# Display_V1_2.net
KiCad netlist of a schematic drawn in EAGLE
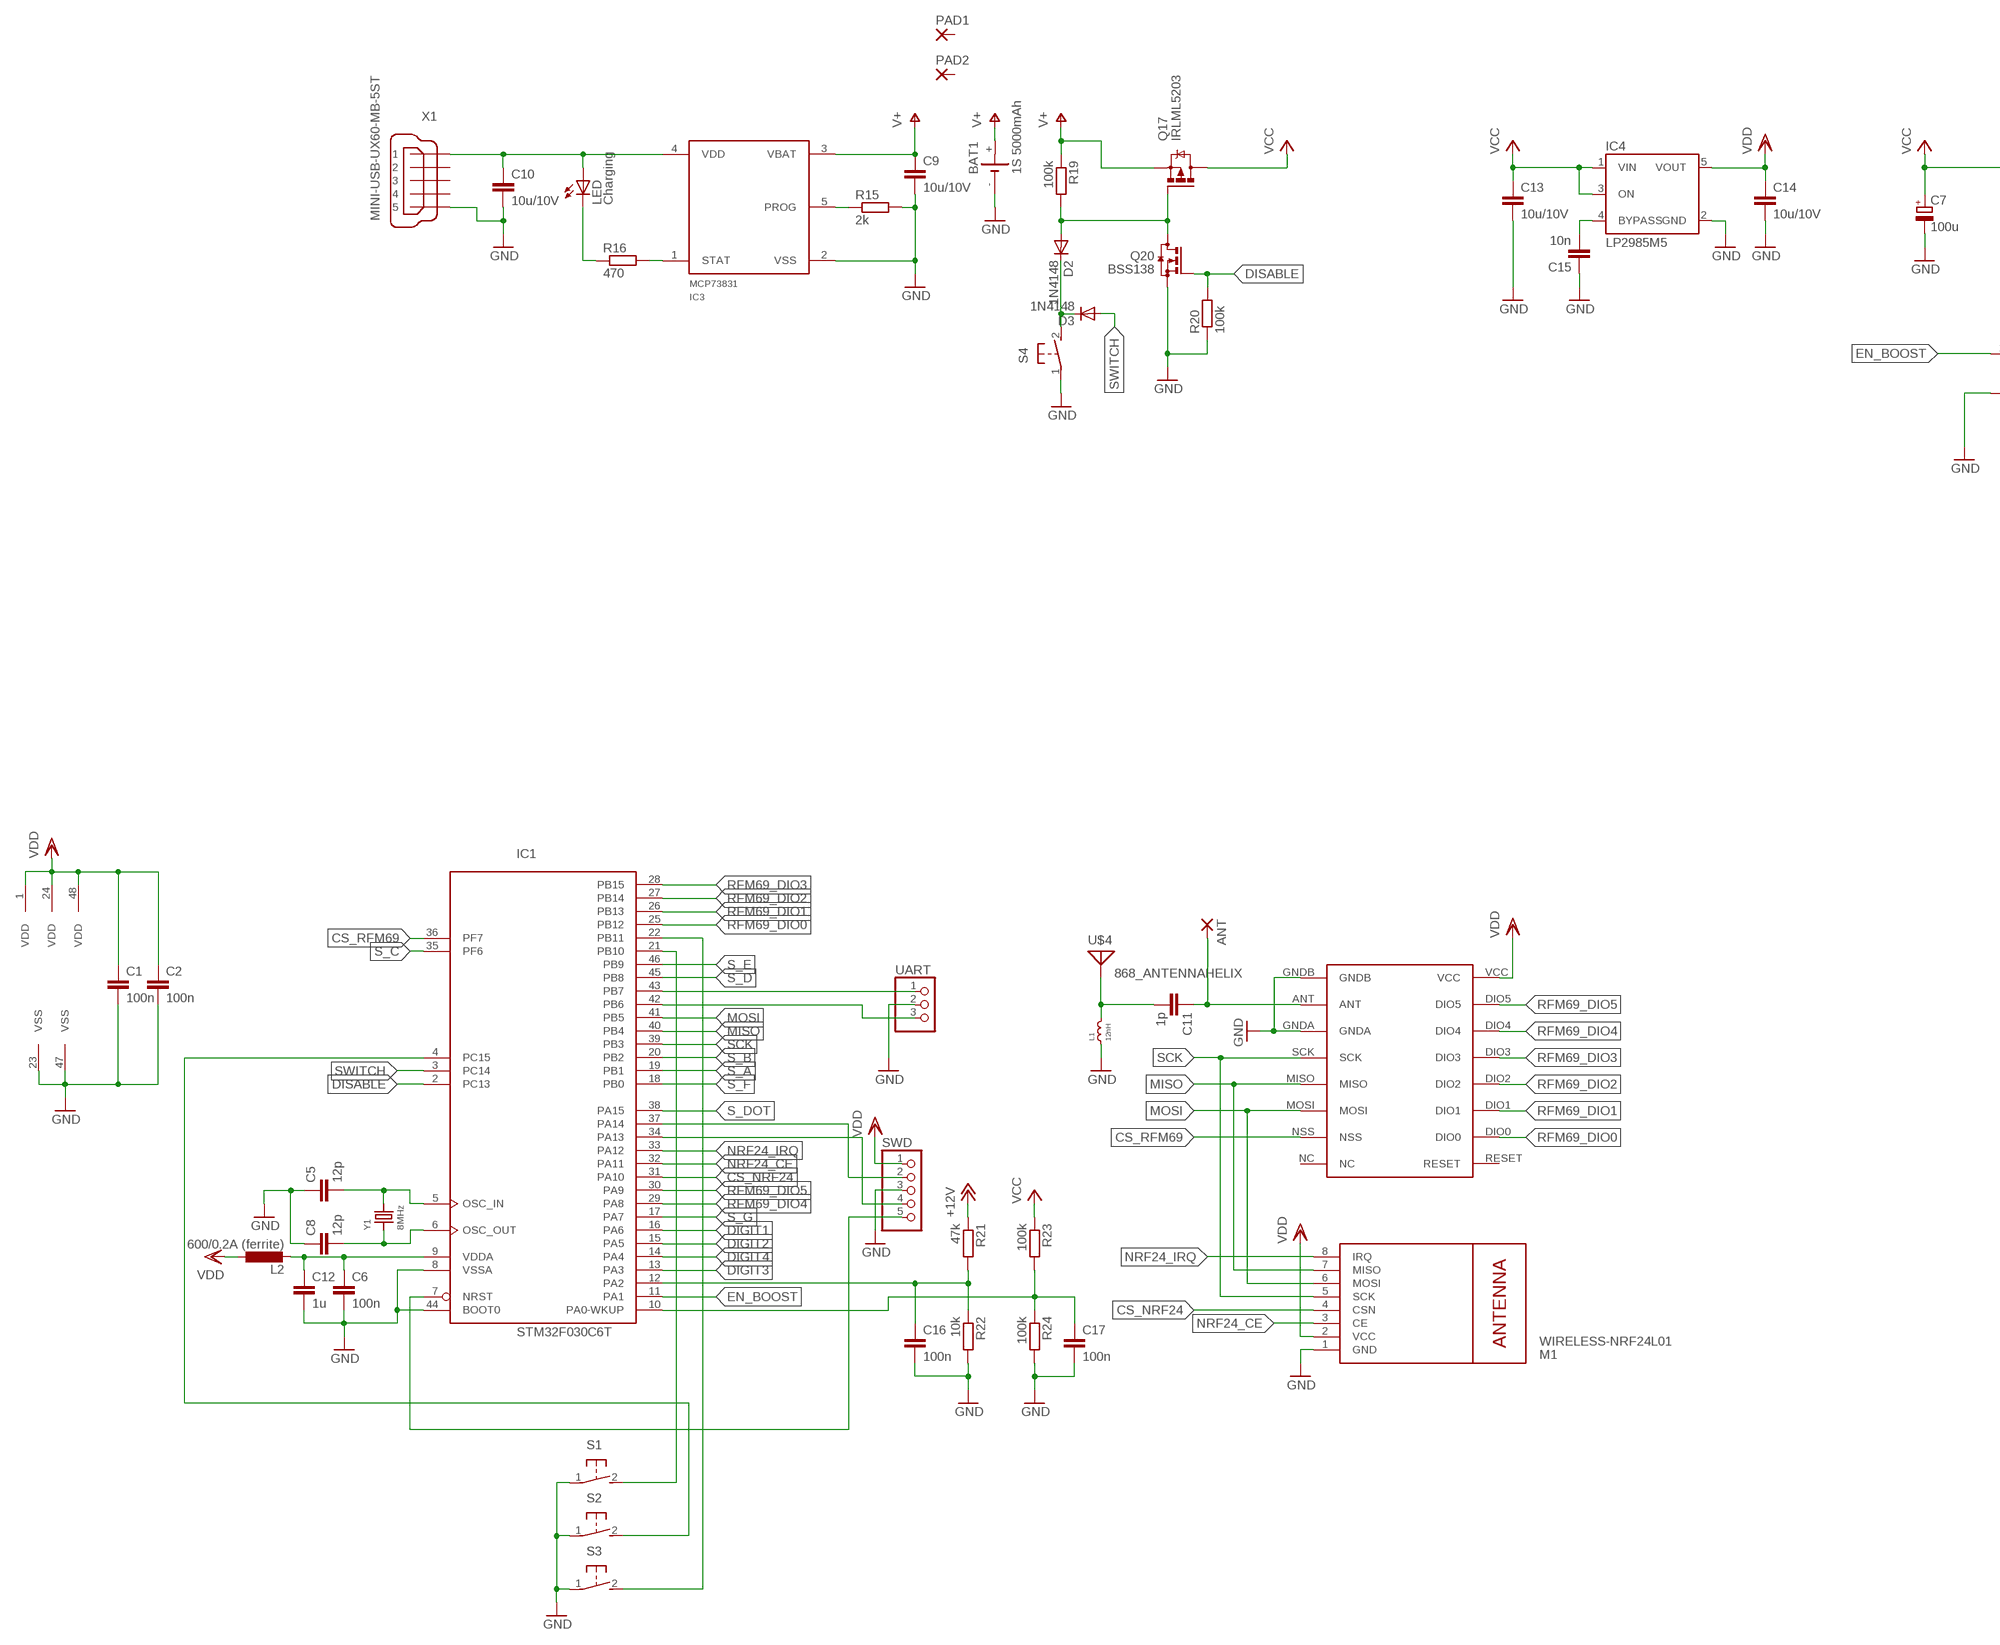
[diagram p0: schematic, sheet 1, part 1 of 2]
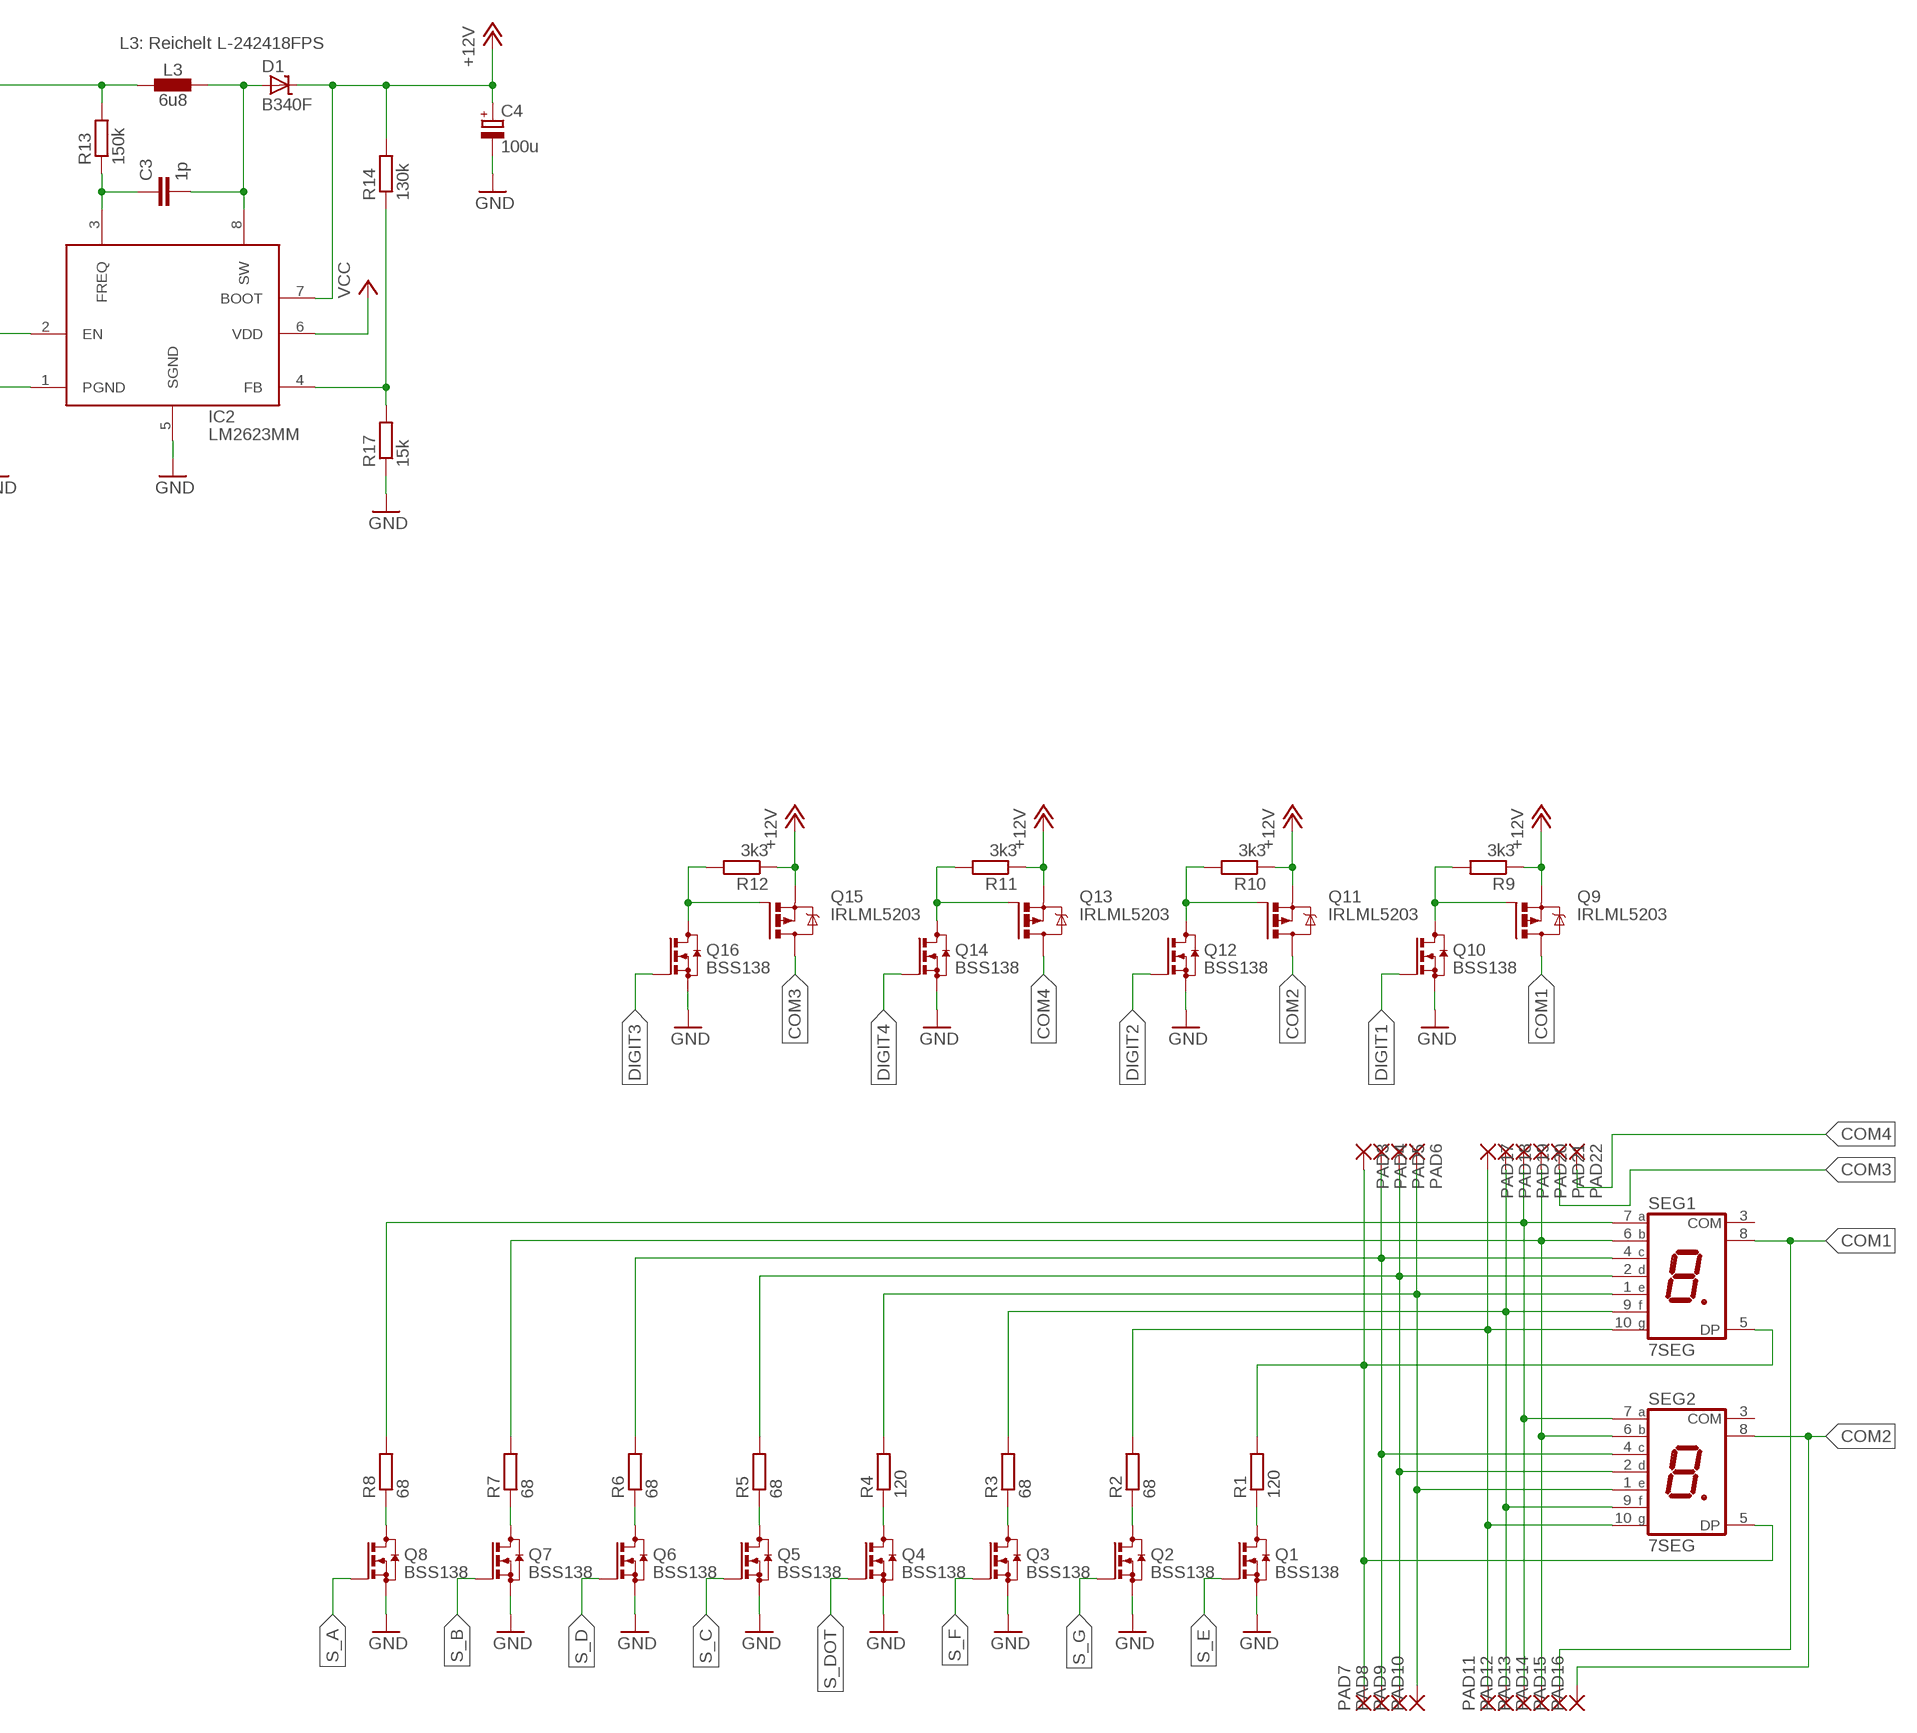
[diagram p1: schematic, sheet 1, part 2 of 2]

(export (version "E")
  (design (tool "Eeschema 10.0.6"))
  (components
    (comp (ref "ANT")
      (value "1,6/0,8")
      (footprint "eagle-import:1,6_0,8")
      (libsource (lib "eagle-import") (part "1,6/0,8"))
    )
    (comp (ref "BAT1")
      (value "1S 5000mAh")
      (footprint "eagle-import:1S_5000MAH")
      (libsource (lib "eagle-import") (part "LIPO"))
    )
    (comp (ref "C1")
      (value "100n")
      (footprint "eagle-import:C0603K")
      (libsource (lib "eagle-import") (part "C-EUC0603K"))
    )
    (comp (ref "C2")
      (value "100n")
      (footprint "eagle-import:C0603K")
      (libsource (lib "eagle-import") (part "C-EUC0603K"))
    )
    (comp (ref "C3")
      (value "1p")
      (footprint "eagle-import:C0603")
      (libsource (lib "eagle-import") (part "C-EUC0603"))
    )
    (comp (ref "C4")
      (value "100u")
      (footprint "eagle-import:153CLV-0605")
      (libsource (lib "eagle-import") (part "CPOL-EU153CLV-0605"))
    )
    (comp (ref "C5")
      (value "12p")
      (footprint "eagle-import:C0603")
      (libsource (lib "eagle-import") (part "C-EUC0603"))
    )
    (comp (ref "C6")
      (value "100n")
      (footprint "eagle-import:C0603")
      (libsource (lib "eagle-import") (part "C-EUC0603"))
    )
    (comp (ref "C7")
      (value "100u")
      (footprint "eagle-import:153CLV-0605")
      (libsource (lib "eagle-import") (part "CPOL-EU153CLV-0605"))
    )
    (comp (ref "C8")
      (value "12p")
      (footprint "eagle-import:C0603")
      (libsource (lib "eagle-import") (part "C-EUC0603"))
    )
    (comp (ref "C9")
      (value "10u/10V")
      (footprint "eagle-import:C1206")
      (libsource (lib "eagle-import") (part "C-EUC1206"))
    )
    (comp (ref "C10")
      (value "10u/10V")
      (footprint "eagle-import:C1206")
      (libsource (lib "eagle-import") (part "C-EUC1206"))
    )
    (comp (ref "C11")
      (value "1p")
      (footprint "eagle-import:C0603")
      (libsource (lib "eagle-import") (part "C-EUC0603"))
    )
    (comp (ref "C12")
      (value "1u")
      (footprint "eagle-import:C0603")
      (libsource (lib "eagle-import") (part "C-EUC0603"))
    )
    (comp (ref "C13")
      (value "10u/10V")
      (footprint "eagle-import:C1206")
      (libsource (lib "eagle-import") (part "C-EUC1206"))
    )
    (comp (ref "C14")
      (value "10u/10V")
      (footprint "eagle-import:C1206")
      (libsource (lib "eagle-import") (part "C-EUC1206"))
    )
    (comp (ref "C15")
      (value "10n")
      (footprint "eagle-import:C0603")
      (libsource (lib "eagle-import") (part "C-EUC0603"))
    )
    (comp (ref "C16")
      (value "100n")
      (footprint "eagle-import:C0603")
      (libsource (lib "eagle-import") (part "C-EUC0603"))
    )
    (comp (ref "C17")
      (value "100n")
      (footprint "eagle-import:C0603")
      (libsource (lib "eagle-import") (part "C-EUC0603"))
    )
    (comp (ref "D1")
      (value "B340F")
      (footprint "eagle-import:SMC")
      (libsource (lib "eagle-import") (part "SD-SMC"))
    )
    (comp (ref "D2")
      (value "1N4148")
      (footprint "eagle-import:MINIMELF")
      (libsource (lib "eagle-import") (part "DIODE-MINIMELF"))
    )
    (comp (ref "D3")
      (value "1N4148")
      (footprint "eagle-import:MINIMELF")
      (libsource (lib "eagle-import") (part "DIODE-MINIMELF"))
    )
    (comp (ref "IC1")
      (value "STM32F030C6T")
      (footprint "eagle-import:LQFP48")
      (libsource (lib "eagle-import") (part "STM32F030CT6"))
    )
    (comp (ref "IC2")
      (value "LM2623MM")
      (footprint "eagle-import:MSOP08")
      (libsource (lib "eagle-import") (part "LM2623MM"))
    )
    (comp (ref "IC3")
      (value "MCP73831")
      (footprint "eagle-import:SOT23-5")
      (libsource (lib "eagle-import") (part "MCP73831"))
    )
    (comp (ref "IC4")
      (value "LP2985M5")
      (footprint "eagle-import:SOT23-5")
      (libsource (lib "eagle-import") (part "LP2985M5"))
    )
    (comp (ref "L1")
      (value "12nH")
      (footprint "eagle-import:0603")
      (libsource (lib "eagle-import") (part "RF-INDUCTOR.0603"))
    )
    (comp (ref "L2")
      (value "600/0.2A (ferrite)")
      (footprint "eagle-import:L2012C")
      (libsource (lib "eagle-import") (part "L-EUL2012C"))
    )
    (comp (ref "L3")
      (value "6u8")
      (footprint "eagle-import:L_NR60XX")
      (libsource (lib "eagle-import") (part "INDUCTOR-NR60XX"))
    )
    (comp (ref "LED")
      (value "Charging")
      (footprint "eagle-import:CHIPLED_0603")
      (libsource (lib "eagle-import") (part "LEDCHIPLED_0603"))
    )
    (comp (ref "M1")
      (value "WIRELESS-NRF24L01")
      (footprint "eagle-import:WIRELESS-NRF24L01")
      (libsource (lib "eagle-import") (part "WIRELESS-NRF24L01"))
    )
    (comp (ref "PAD1")
      (value "2,54/1,0")
      (footprint "eagle-import:2,54_1,0")
      (libsource (lib "eagle-import") (part "2,54/1,0"))
    )
    (comp (ref "PAD2")
      (value "2,54/1,0")
      (footprint "eagle-import:2,54_1,0")
      (libsource (lib "eagle-import") (part "2,54/1,0"))
    )
    (comp (ref "PAD3")
      (value "SMD2")
      (footprint "eagle-import:SMD1,27-2,54")
      (libsource (lib "eagle-import") (part "SMD2"))
    )
    (comp (ref "PAD4")
      (value "SMD2")
      (footprint "eagle-import:SMD1,27-2,54")
      (libsource (lib "eagle-import") (part "SMD2"))
    )
    (comp (ref "PAD5")
      (value "SMD2")
      (footprint "eagle-import:SMD1,27-2,54")
      (libsource (lib "eagle-import") (part "SMD2"))
    )
    (comp (ref "PAD6")
      (value "SMD2")
      (footprint "eagle-import:SMD1,27-2,54")
      (libsource (lib "eagle-import") (part "SMD2"))
    )
    (comp (ref "PAD7")
      (value "SMD2")
      (footprint "eagle-import:SMD1,27-2,54")
      (libsource (lib "eagle-import") (part "SMD2"))
    )
    (comp (ref "PAD8")
      (value "SMD2")
      (footprint "eagle-import:SMD1,27-2,54")
      (libsource (lib "eagle-import") (part "SMD2"))
    )
    (comp (ref "PAD9")
      (value "SMD2")
      (footprint "eagle-import:SMD1,27-2,54")
      (libsource (lib "eagle-import") (part "SMD2"))
    )
    (comp (ref "PAD10")
      (value "SMD2")
      (footprint "eagle-import:SMD1,27-2,54")
      (libsource (lib "eagle-import") (part "SMD2"))
    )
    (comp (ref "PAD11")
      (value "SMD2")
      (footprint "eagle-import:SMD1,27-2,54")
      (libsource (lib "eagle-import") (part "SMD2"))
    )
    (comp (ref "PAD12")
      (value "SMD2")
      (footprint "eagle-import:SMD1,27-2,54")
      (libsource (lib "eagle-import") (part "SMD2"))
    )
    (comp (ref "PAD13")
      (value "SMD2")
      (footprint "eagle-import:SMD1,27-2,54")
      (libsource (lib "eagle-import") (part "SMD2"))
    )
    (comp (ref "PAD14")
      (value "SMD2")
      (footprint "eagle-import:SMD1,27-2,54")
      (libsource (lib "eagle-import") (part "SMD2"))
    )
    (comp (ref "PAD15")
      (value "SMD2")
      (footprint "eagle-import:SMD1,27-2,54")
      (libsource (lib "eagle-import") (part "SMD2"))
    )
    (comp (ref "PAD16")
      (value "SMD2")
      (footprint "eagle-import:SMD1,27-2,54")
      (libsource (lib "eagle-import") (part "SMD2"))
    )
    (comp (ref "PAD17")
      (value "SMD2")
      (footprint "eagle-import:SMD1,27-2,54")
      (libsource (lib "eagle-import") (part "SMD2"))
    )
    (comp (ref "PAD18")
      (value "SMD2")
      (footprint "eagle-import:SMD1,27-2,54")
      (libsource (lib "eagle-import") (part "SMD2"))
    )
    (comp (ref "PAD19")
      (value "SMD2")
      (footprint "eagle-import:SMD1,27-2,54")
      (libsource (lib "eagle-import") (part "SMD2"))
    )
    (comp (ref "PAD20")
      (value "SMD2")
      (footprint "eagle-import:SMD1,27-2,54")
      (libsource (lib "eagle-import") (part "SMD2"))
    )
    (comp (ref "PAD21")
      (value "SMD2")
      (footprint "eagle-import:SMD1,27-2,54")
      (libsource (lib "eagle-import") (part "SMD2"))
    )
    (comp (ref "PAD22")
      (value "SMD2")
      (footprint "eagle-import:SMD1,27-2,54")
      (libsource (lib "eagle-import") (part "SMD2"))
    )
    (comp (ref "Q1")
      (value "BSS138")
      (footprint "eagle-import:SOT23")
      (libsource (lib "eagle-import") (part "BSS123"))
    )
    (comp (ref "Q2")
      (value "BSS138")
      (footprint "eagle-import:SOT23")
      (libsource (lib "eagle-import") (part "BSS123"))
    )
    (comp (ref "Q3")
      (value "BSS138")
      (footprint "eagle-import:SOT23")
      (libsource (lib "eagle-import") (part "BSS123"))
    )
    (comp (ref "Q4")
      (value "BSS138")
      (footprint "eagle-import:SOT23")
      (libsource (lib "eagle-import") (part "BSS123"))
    )
    (comp (ref "Q5")
      (value "BSS138")
      (footprint "eagle-import:SOT23")
      (libsource (lib "eagle-import") (part "BSS123"))
    )
    (comp (ref "Q6")
      (value "BSS138")
      (footprint "eagle-import:SOT23")
      (libsource (lib "eagle-import") (part "BSS123"))
    )
    (comp (ref "Q7")
      (value "BSS138")
      (footprint "eagle-import:SOT23")
      (libsource (lib "eagle-import") (part "BSS123"))
    )
    (comp (ref "Q8")
      (value "BSS138")
      (footprint "eagle-import:SOT23")
      (libsource (lib "eagle-import") (part "BSS123"))
    )
    (comp (ref "Q9")
      (value "IRLML5203")
      (footprint "eagle-import:MICRO3")
      (libsource (lib "eagle-import") (part "IRLML5203"))
    )
    (comp (ref "Q10")
      (value "BSS138")
      (footprint "eagle-import:SOT23")
      (libsource (lib "eagle-import") (part "BSS123"))
    )
    (comp (ref "Q11")
      (value "IRLML5203")
      (footprint "eagle-import:MICRO3")
      (libsource (lib "eagle-import") (part "IRLML5203"))
    )
    (comp (ref "Q12")
      (value "BSS138")
      (footprint "eagle-import:SOT23")
      (libsource (lib "eagle-import") (part "BSS123"))
    )
    (comp (ref "Q13")
      (value "IRLML5203")
      (footprint "eagle-import:MICRO3")
      (libsource (lib "eagle-import") (part "IRLML5203"))
    )
    (comp (ref "Q14")
      (value "BSS138")
      (footprint "eagle-import:SOT23")
      (libsource (lib "eagle-import") (part "BSS123"))
    )
    (comp (ref "Q15")
      (value "IRLML5203")
      (footprint "eagle-import:MICRO3")
      (libsource (lib "eagle-import") (part "IRLML5203"))
    )
    (comp (ref "Q16")
      (value "BSS138")
      (footprint "eagle-import:SOT23")
      (libsource (lib "eagle-import") (part "BSS123"))
    )
    (comp (ref "Q17")
      (value "IRLML5203")
      (footprint "eagle-import:MICRO3")
      (libsource (lib "eagle-import") (part "IRLML5203"))
    )
    (comp (ref "Q20")
      (value "BSS138")
      (footprint "eagle-import:SOT23")
      (libsource (lib "eagle-import") (part "BSS123"))
    )
    (comp (ref "R1")
      (value "120")
      (footprint "eagle-import:R1206")
      (libsource (lib "eagle-import") (part "R-EU_R1206"))
    )
    (comp (ref "R2")
      (value "68")
      (footprint "eagle-import:R1206")
      (libsource (lib "eagle-import") (part "R-EU_R1206"))
    )
    (comp (ref "R3")
      (value "68")
      (footprint "eagle-import:R1206")
      (libsource (lib "eagle-import") (part "R-EU_R1206"))
    )
    (comp (ref "R4")
      (value "120")
      (footprint "eagle-import:R1206")
      (libsource (lib "eagle-import") (part "R-EU_R1206"))
    )
    (comp (ref "R5")
      (value "68")
      (footprint "eagle-import:R1206")
      (libsource (lib "eagle-import") (part "R-EU_R1206"))
    )
    (comp (ref "R6")
      (value "68")
      (footprint "eagle-import:R1206")
      (libsource (lib "eagle-import") (part "R-EU_R1206"))
    )
    (comp (ref "R7")
      (value "68")
      (footprint "eagle-import:R1206")
      (libsource (lib "eagle-import") (part "R-EU_R1206"))
    )
    (comp (ref "R8")
      (value "68")
      (footprint "eagle-import:R1206")
      (libsource (lib "eagle-import") (part "R-EU_R1206"))
    )
    (comp (ref "R9")
      (value "3k3")
      (footprint "eagle-import:R0603")
      (libsource (lib "eagle-import") (part "resistor_R-EU_R0603"))
    )
    (comp (ref "R10")
      (value "3k3")
      (footprint "eagle-import:R0603")
      (libsource (lib "eagle-import") (part "resistor_R-EU_R0603"))
    )
    (comp (ref "R11")
      (value "3k3")
      (footprint "eagle-import:R0603")
      (libsource (lib "eagle-import") (part "resistor_R-EU_R0603"))
    )
    (comp (ref "R12")
      (value "3k3")
      (footprint "eagle-import:R0603")
      (libsource (lib "eagle-import") (part "resistor_R-EU_R0603"))
    )
    (comp (ref "R13")
      (value "150k")
      (footprint "eagle-import:R0603")
      (libsource (lib "eagle-import") (part "R-EU_R0603"))
    )
    (comp (ref "R14")
      (value "130k")
      (footprint "eagle-import:R0603")
      (libsource (lib "eagle-import") (part "R-EU_R0603"))
    )
    (comp (ref "R15")
      (value "2k")
      (footprint "eagle-import:R0603")
      (libsource (lib "eagle-import") (part "R-EU_R0603"))
    )
    (comp (ref "R16")
      (value "470")
      (footprint "eagle-import:R0603")
      (libsource (lib "eagle-import") (part "R-EU_R0603"))
    )
    (comp (ref "R17")
      (value "15k")
      (footprint "eagle-import:R0603")
      (libsource (lib "eagle-import") (part "R-EU_R0603"))
    )
    (comp (ref "R19")
      (value "100k")
      (footprint "eagle-import:R0603")
      (libsource (lib "eagle-import") (part "R-EU_R0603"))
    )
    (comp (ref "R20")
      (value "100k")
      (footprint "eagle-import:R0603")
      (libsource (lib "eagle-import") (part "R-EU_R0603"))
    )
    (comp (ref "R21")
      (value "47k")
      (footprint "eagle-import:R0603")
      (libsource (lib "eagle-import") (part "R-EU_R0603"))
    )
    (comp (ref "R22")
      (value "10k")
      (footprint "eagle-import:R0603")
      (libsource (lib "eagle-import") (part "R-EU_R0603"))
    )
    (comp (ref "R23")
      (value "100k")
      (footprint "eagle-import:R0603")
      (libsource (lib "eagle-import") (part "R-EU_R0603"))
    )
    (comp (ref "R24")
      (value "100k")
      (footprint "eagle-import:R0603")
      (libsource (lib "eagle-import") (part "R-EU_R0603"))
    )
    (comp (ref "S1")
      (value "31-XX")
      (footprint "eagle-import:B3F-31XX")
      (fields (field (name "MPN") "B3F-3100"))
      (libsource (lib "eagle-import") (part "31-XX"))
    )
    (comp (ref "S2")
      (value "31-XX")
      (footprint "eagle-import:B3F-31XX")
      (fields (field (name "MPN") "B3F-3100"))
      (libsource (lib "eagle-import") (part "31-XX"))
    )
    (comp (ref "S3")
      (value "31-XX")
      (footprint "eagle-import:B3F-31XX")
      (fields (field (name "MPN") "B3F-3100"))
      (libsource (lib "eagle-import") (part "31-XX"))
    )
    (comp (ref "S4")
      (value "31-XX")
      (footprint "eagle-import:B3F-31XX")
      (fields (field (name "MPN") "B3F-3100"))
      (libsource (lib "eagle-import") (part "31-XX"))
    )
    (comp (ref "SEG1")
      (value "7SEG")
      (footprint "eagle-import:7SEG_70_40")
      (libsource (lib "eagle-import") (part "7SEG"))
    )
    (comp (ref "SEG2")
      (value "7SEG")
      (footprint "eagle-import:7SEG_70_40")
      (libsource (lib "eagle-import") (part "7SEG"))
    )
    (comp (ref "SWD")
      (value "PINHD-1X5")
      (footprint "eagle-import:1X05")
      (libsource (lib "eagle-import") (part "PINHD-1X5"))
    )
    (comp (ref "U$1")
      (value "RFM69HW")
      (footprint "eagle-import:RFM")
      (libsource (lib "eagle-import") (part "RFM69HW"))
    )
    (comp (ref "U$4")
      (value "868_ANTENNAHELIX")
      (footprint "eagle-import:HELIX_868")
      (libsource (lib "eagle-import") (part "868_ANTENNAHELIX"))
    )
    (comp (ref "UART")
      (value "PINHD-1X3")
      (footprint "eagle-import:1X03")
      (libsource (lib "eagle-import") (part "PINHD-1X3"))
    )
    (comp (ref "X1")
      (value "MINI-USB-UX60-MB-5ST")
      (footprint "eagle-import:UX60-MB-5ST")
      (libsource (lib "eagle-import") (part "MINI-USB-UX60-MB-5ST"))
    )
    (comp (ref "Y1")
      (value "8MHz")
      (footprint "eagle-import:3.2X2.5MM")
      (libsource (lib "eagle-import") (part "CRYSTAL.3.2X2.5MM"))
    )
  )
  (nets
    (net (code "1") (name "+12V") (class "Default")
      (node (ref "C4") (pin "+") (pinfunction "+_+") (pintype "passive"))
      (node (ref "D1") (pin "C") (pinfunction "C_C") (pintype "passive"))
      (node (ref "IC2") (pin "7") (pinfunction "BOOT_7") (pintype "bidirectional"))
      (node (ref "Q11") (pin "2") (pinfunction "S_2") (pintype "passive"))
      (node (ref "Q13") (pin "2") (pinfunction "S_2") (pintype "passive"))
      (node (ref "Q15") (pin "2") (pinfunction "S_2") (pintype "passive"))
      (node (ref "Q9") (pin "2") (pinfunction "S_2") (pintype "passive"))
      (node (ref "R10") (pin "1") (pinfunction "1_1") (pintype "passive"))
      (node (ref "R11") (pin "1") (pinfunction "1_1") (pintype "passive"))
      (node (ref "R12") (pin "1") (pinfunction "1_1") (pintype "passive"))
      (node (ref "R14") (pin "2") (pinfunction "2_2") (pintype "passive"))
      (node (ref "R21") (pin "1") (pinfunction "1_1") (pintype "passive"))
      (node (ref "R9") (pin "1") (pinfunction "1_1") (pintype "passive"))
    )
    (net (code "2") (name "COM1") (class "Default")
      (node (ref "PAD15") (pin "1") (pinfunction "P_1") (pintype "passive"))
      (node (ref "Q9") (pin "3") (pinfunction "D_3") (pintype "passive"))
      (node (ref "SEG1") (pin "8") (pinfunction "COM_8") (pintype "passive"))
    )
    (net (code "3") (name "COM2") (class "Default")
      (node (ref "PAD16") (pin "1") (pinfunction "P_1") (pintype "passive"))
      (node (ref "Q11") (pin "3") (pinfunction "D_3") (pintype "passive"))
      (node (ref "SEG2") (pin "8") (pinfunction "COM_8") (pintype "passive"))
    )
    (net (code "4") (name "COM3") (class "Default")
      (node (ref "PAD21") (pin "1") (pinfunction "P_1") (pintype "passive"))
      (node (ref "Q15") (pin "3") (pinfunction "D_3") (pintype "passive"))
    )
    (net (code "5") (name "COM4") (class "Default")
      (node (ref "PAD22") (pin "1") (pinfunction "P_1") (pintype "passive"))
      (node (ref "Q13") (pin "3") (pinfunction "D_3") (pintype "passive"))
    )
    (net (code "6") (name "CS_NRF24") (class "Default")
      (node (ref "IC1") (pin "31") (pinfunction "PA10_31") (pintype "bidirectional"))
      (node (ref "M1") (pin "4") (pinfunction "CSN_4") (pintype "bidirectional"))
    )
    (net (code "7") (name "CS_RFM69") (class "Default")
      (node (ref "IC1") (pin "36") (pinfunction "PF7_36") (pintype "bidirectional"))
      (node (ref "U$1") (pin "NSS") (pinfunction "NSS_NSS") (pintype "bidirectional"))
    )
    (net (code "8") (name "DIGIT1") (class "Default")
      (node (ref "IC1") (pin "16") (pinfunction "PA6_16") (pintype "bidirectional"))
      (node (ref "Q10") (pin "1") (pinfunction "G_1") (pintype "passive"))
    )
    (net (code "9") (name "DIGIT2") (class "Default")
      (node (ref "IC1") (pin "15") (pinfunction "PA5_15") (pintype "bidirectional"))
      (node (ref "Q12") (pin "1") (pinfunction "G_1") (pintype "passive"))
    )
    (net (code "10") (name "DIGIT3") (class "Default")
      (node (ref "IC1") (pin "13") (pinfunction "PA3_13") (pintype "bidirectional"))
      (node (ref "Q16") (pin "1") (pinfunction "G_1") (pintype "passive"))
    )
    (net (code "11") (name "DIGIT4") (class "Default")
      (node (ref "IC1") (pin "14") (pinfunction "PA4_14") (pintype "bidirectional"))
      (node (ref "Q14") (pin "1") (pinfunction "G_1") (pintype "passive"))
    )
    (net (code "12") (name "DISABLE") (class "Default")
      (node (ref "IC1") (pin "2") (pinfunction "PC13_2") (pintype "bidirectional"))
      (node (ref "Q20") (pin "1") (pinfunction "G_1") (pintype "passive"))
      (node (ref "R20") (pin "2") (pinfunction "2_2") (pintype "passive"))
    )
    (net (code "13") (name "EN_BOOST") (class "Default")
      (node (ref "IC1") (pin "11") (pinfunction "PA1_11") (pintype "bidirectional"))
      (node (ref "IC2") (pin "2") (pinfunction "EN_2") (pintype "bidirectional"))
    )
    (net (code "14") (name "GND") (class "Default")
      (node (ref "BAT1") (pin "-") (pinfunction "-_-") (pintype "passive"))
      (node (ref "C1") (pin "2") (pinfunction "2_2") (pintype "passive"))
      (node (ref "C10") (pin "2") (pinfunction "2_2") (pintype "passive"))
      (node (ref "C12") (pin "2") (pinfunction "2_2") (pintype "passive"))
      (node (ref "C13") (pin "2") (pinfunction "2_2") (pintype "passive"))
      (node (ref "C14") (pin "2") (pinfunction "2_2") (pintype "passive"))
      (node (ref "C15") (pin "1") (pinfunction "1_1") (pintype "passive"))
      (node (ref "C16") (pin "2") (pinfunction "2_2") (pintype "passive"))
      (node (ref "C17") (pin "2") (pinfunction "2_2") (pintype "passive"))
      (node (ref "C2") (pin "2") (pinfunction "2_2") (pintype "passive"))
      (node (ref "C4") (pin "-") (pinfunction "-_-") (pintype "passive"))
      (node (ref "C5") (pin "1") (pinfunction "1_1") (pintype "passive"))
      (node (ref "C6") (pin "2") (pinfunction "2_2") (pintype "passive"))
      (node (ref "C7") (pin "-") (pinfunction "-_-") (pintype "passive"))
      (node (ref "C8") (pin "1") (pinfunction "1_1") (pintype "passive"))
      (node (ref "C9") (pin "2") (pinfunction "2_2") (pintype "passive"))
      (node (ref "IC1") (pin "23") (pinfunction "VSS_23") (pintype "power_in"))
      (node (ref "IC1") (pin "44") (pinfunction "BOOT0_44") (pintype "input"))
      (node (ref "IC1") (pin "47") (pinfunction "VSS_47") (pintype "power_in"))
      (node (ref "IC1") (pin "8") (pinfunction "VSSA_8") (pintype "power_in"))
      (node (ref "IC2") (pin "1") (pinfunction "PGND_1") (pintype "bidirectional"))
      (node (ref "IC2") (pin "5") (pinfunction "SGND_5") (pintype "bidirectional"))
      (node (ref "IC3") (pin "2") (pinfunction "VSS_2") (pintype "bidirectional"))
      (node (ref "IC4") (pin "2") (pinfunction "GND_2") (pintype "power_in"))
      (node (ref "L1") (pin "1") (pinfunction "1_1") (pintype "passive"))
      (node (ref "M1") (pin "1") (pinfunction "GND_1") (pintype "power_in"))
      (node (ref "Q1") (pin "2") (pinfunction "S_2") (pintype "passive"))
      (node (ref "Q10") (pin "2") (pinfunction "S_2") (pintype "passive"))
      (node (ref "Q12") (pin "2") (pinfunction "S_2") (pintype "passive"))
      (node (ref "Q14") (pin "2") (pinfunction "S_2") (pintype "passive"))
      (node (ref "Q16") (pin "2") (pinfunction "S_2") (pintype "passive"))
      (node (ref "Q2") (pin "2") (pinfunction "S_2") (pintype "passive"))
      (node (ref "Q20") (pin "2") (pinfunction "S_2") (pintype "passive"))
      (node (ref "Q3") (pin "2") (pinfunction "S_2") (pintype "passive"))
      (node (ref "Q4") (pin "2") (pinfunction "S_2") (pintype "passive"))
      (node (ref "Q5") (pin "2") (pinfunction "S_2") (pintype "passive"))
      (node (ref "Q6") (pin "2") (pinfunction "S_2") (pintype "passive"))
      (node (ref "Q7") (pin "2") (pinfunction "S_2") (pintype "passive"))
      (node (ref "Q8") (pin "2") (pinfunction "S_2") (pintype "passive"))
      (node (ref "R15") (pin "2") (pinfunction "2_2") (pintype "passive"))
      (node (ref "R17") (pin "1") (pinfunction "1_1") (pintype "passive"))
      (node (ref "R20") (pin "1") (pinfunction "1_1") (pintype "passive"))
      (node (ref "R22") (pin "2") (pinfunction "2_2") (pintype "passive"))
      (node (ref "R24") (pin "2") (pinfunction "2_2") (pintype "passive"))
      (node (ref "S1") (pin "1") (pinfunction "P_1") (pintype "passive"))
      (node (ref "S2") (pin "1") (pinfunction "P_1") (pintype "passive"))
      (node (ref "S3") (pin "1") (pinfunction "P_1") (pintype "passive"))
      (node (ref "S4") (pin "1") (pinfunction "P_1") (pintype "passive"))
      (node (ref "SWD") (pin "3") (pinfunction "3_3") (pintype "passive"))
      (node (ref "U$1") (pin "GNDA") (pinfunction "GNDA_GNDA") (pintype "bidirectional"))
      (node (ref "U$1") (pin "GNDB") (pinfunction "GNDB_GNDB") (pintype "bidirectional"))
      (node (ref "UART") (pin "2") (pinfunction "2_2") (pintype "passive"))
      (node (ref "X1") (pin "5") (pinfunction "5_5") (pintype "input"))
    )
    (net (code "15") (name "MISO") (class "Default")
      (node (ref "IC1") (pin "40") (pinfunction "PB4_40") (pintype "bidirectional"))
      (node (ref "M1") (pin "7") (pinfunction "MISO_7") (pintype "bidirectional"))
      (node (ref "U$1") (pin "MISO") (pinfunction "MISO_MISO") (pintype "bidirectional"))
    )
    (net (code "16") (name "MOSI") (class "Default")
      (node (ref "IC1") (pin "41") (pinfunction "PB5_41") (pintype "bidirectional"))
      (node (ref "M1") (pin "6") (pinfunction "MOSI_6") (pintype "bidirectional"))
      (node (ref "U$1") (pin "MOSI") (pinfunction "MOSI_MOSI") (pintype "bidirectional"))
    )
    (net (code "17") (name "NRF24_CE") (class "Default")
      (node (ref "IC1") (pin "32") (pinfunction "PA11_32") (pintype "bidirectional"))
      (node (ref "M1") (pin "3") (pinfunction "CE_3") (pintype "bidirectional"))
    )
    (net (code "18") (name "NRF24_IRQ") (class "Default")
      (node (ref "IC1") (pin "33") (pinfunction "PA12_33") (pintype "bidirectional"))
      (node (ref "M1") (pin "8") (pinfunction "IRQ_8") (pintype "bidirectional"))
    )
    (net (code "19") (name "Net-(ANT-P)") (class "Default")
      (node (ref "ANT") (pin "1") (pinfunction "P_1") (pintype "passive"))
      (node (ref "C11") (pin "1") (pinfunction "1_1") (pintype "passive"))
      (node (ref "U$1") (pin "ANT") (pinfunction "ANT_ANT") (pintype "bidirectional"))
    )
    (net (code "20") (name "Net-(C11-Pad2)") (class "Default")
      (node (ref "C11") (pin "2") (pinfunction "2_2") (pintype "passive"))
      (node (ref "L1") (pin "2") (pinfunction "2_2") (pintype "passive"))
      (node (ref "U$4") (pin "ANT") (pinfunction "1_ANT") (pintype "output"))
      (node (ref "U$4") (pin "P$10") (pinfunction "1_P$10") (pintype "output"))
      (node (ref "U$4") (pin "P$11") (pinfunction "1_P$11") (pintype "output"))
      (node (ref "U$4") (pin "P$12") (pinfunction "1_P$12") (pintype "output"))
      (node (ref "U$4") (pin "P$13") (pinfunction "1_P$13") (pintype "output"))
      (node (ref "U$4") (pin "P$14") (pinfunction "1_P$14") (pintype "output"))
      (node (ref "U$4") (pin "P$15") (pinfunction "1_P$15") (pintype "output"))
      (node (ref "U$4") (pin "P$16") (pinfunction "1_P$16") (pintype "output"))
      (node (ref "U$4") (pin "P$17") (pinfunction "1_P$17") (pintype "output"))
      (node (ref "U$4") (pin "P$18") (pinfunction "1_P$18") (pintype "output"))
      (node (ref "U$4") (pin "P$19") (pinfunction "1_P$19") (pintype "output"))
      (node (ref "U$4") (pin "P$2") (pinfunction "1_P$2") (pintype "output"))
      (node (ref "U$4") (pin "P$20") (pinfunction "1_P$20") (pintype "output"))
      (node (ref "U$4") (pin "P$3") (pinfunction "1_P$3") (pintype "output"))
      (node (ref "U$4") (pin "P$4") (pinfunction "1_P$4") (pintype "output"))
      (node (ref "U$4") (pin "P$5") (pinfunction "1_P$5") (pintype "output"))
      (node (ref "U$4") (pin "P$6") (pinfunction "1_P$6") (pintype "output"))
      (node (ref "U$4") (pin "P$7") (pinfunction "1_P$7") (pintype "output"))
      (node (ref "U$4") (pin "P$8") (pinfunction "1_P$8") (pintype "output"))
      (node (ref "U$4") (pin "P$9") (pinfunction "1_P$9") (pintype "output"))
    )
    (net (code "21") (name "Net-(IC1A-NRST)") (class "Default")
      (node (ref "IC1") (pin "7") (pinfunction "NRST_7") (pintype "bidirectional"))
      (node (ref "SWD") (pin "5") (pinfunction "5_5") (pintype "passive"))
    )
    (net (code "22") (name "Net-(IC1A-OSC_IN)") (class "Default")
      (node (ref "C5") (pin "2") (pinfunction "2_2") (pintype "passive"))
      (node (ref "IC1") (pin "5") (pinfunction "OSC_IN_5") (pintype "bidirectional"))
      (node (ref "Y1") (pin "3") (pinfunction "2_3") (pintype "passive"))
    )
    (net (code "23") (name "Net-(IC1A-OSC_OUT)") (class "Default")
      (node (ref "C8") (pin "2") (pinfunction "2_2") (pintype "passive"))
      (node (ref "IC1") (pin "6") (pinfunction "OSC_OUT_6") (pintype "bidirectional"))
      (node (ref "Y1") (pin "1") (pinfunction "1_1") (pintype "passive"))
    )
    (net (code "24") (name "Net-(IC1A-PA0-WKUP)") (class "Default")
      (node (ref "C17") (pin "1") (pinfunction "1_1") (pintype "passive"))
      (node (ref "IC1") (pin "10") (pinfunction "PA0-WKUP_10") (pintype "bidirectional"))
      (node (ref "R23") (pin "2") (pinfunction "2_2") (pintype "passive"))
      (node (ref "R24") (pin "1") (pinfunction "1_1") (pintype "passive"))
    )
    (net (code "25") (name "Net-(IC1A-PA2)") (class "Default")
      (node (ref "C16") (pin "1") (pinfunction "1_1") (pintype "passive"))
      (node (ref "IC1") (pin "12") (pinfunction "PA2_12") (pintype "bidirectional"))
      (node (ref "R21") (pin "2") (pinfunction "2_2") (pintype "passive"))
      (node (ref "R22") (pin "1") (pinfunction "1_1") (pintype "passive"))
    )
    (net (code "26") (name "Net-(IC1A-PA13)") (class "Default")
      (node (ref "IC1") (pin "34") (pinfunction "PA13_34") (pintype "bidirectional"))
      (node (ref "SWD") (pin "4") (pinfunction "4_4") (pintype "passive"))
    )
    (net (code "27") (name "Net-(IC1A-PA14)") (class "Default")
      (node (ref "IC1") (pin "37") (pinfunction "PA14_37") (pintype "bidirectional"))
      (node (ref "SWD") (pin "2") (pinfunction "2_2") (pintype "passive"))
    )
    (net (code "28") (name "Net-(IC1A-PB6)") (class "Default")
      (node (ref "IC1") (pin "42") (pinfunction "PB6_42") (pintype "bidirectional"))
      (node (ref "UART") (pin "3") (pinfunction "3_3") (pintype "passive"))
    )
    (net (code "29") (name "Net-(IC1A-PB7)") (class "Default")
      (node (ref "IC1") (pin "43") (pinfunction "PB7_43") (pintype "bidirectional"))
      (node (ref "UART") (pin "1") (pinfunction "1_1") (pintype "passive"))
    )
    (net (code "30") (name "Net-(IC1A-PB10)") (class "Default")
      (node (ref "IC1") (pin "21") (pinfunction "PB10_21") (pintype "bidirectional"))
      (node (ref "S1") (pin "2") (pinfunction "S_2") (pintype "passive"))
    )
    (net (code "31") (name "Net-(IC1A-PB11)") (class "Default")
      (node (ref "IC1") (pin "22") (pinfunction "PB11_22") (pintype "bidirectional"))
      (node (ref "S3") (pin "2") (pinfunction "S_2") (pintype "passive"))
    )
    (net (code "32") (name "Net-(IC1A-PC15)") (class "Default")
      (node (ref "IC1") (pin "4") (pinfunction "PC15_4") (pintype "bidirectional"))
      (node (ref "S2") (pin "2") (pinfunction "S_2") (pintype "passive"))
    )
    (net (code "33") (name "Net-(IC1A-VDDA)") (class "Default")
      (node (ref "C12") (pin "1") (pinfunction "1_1") (pintype "passive"))
      (node (ref "C6") (pin "1") (pinfunction "1_1") (pintype "passive"))
      (node (ref "IC1") (pin "9") (pinfunction "VDDA_9") (pintype "power_in"))
      (node (ref "L2") (pin "2") (pinfunction "2_2") (pintype "passive"))
    )
    (net (code "34") (name "Net-(IC2-FB)") (class "Default")
      (node (ref "IC2") (pin "4") (pinfunction "FB_4") (pintype "bidirectional"))
      (node (ref "R14") (pin "1") (pinfunction "1_1") (pintype "passive"))
      (node (ref "R17") (pin "2") (pinfunction "2_2") (pintype "passive"))
    )
    (net (code "35") (name "Net-(IC2-FREQ)") (class "Default")
      (node (ref "C3") (pin "1") (pinfunction "1_1") (pintype "passive"))
      (node (ref "IC2") (pin "3") (pinfunction "FREQ_3") (pintype "bidirectional"))
      (node (ref "R13") (pin "1") (pinfunction "1_1") (pintype "passive"))
    )
    (net (code "36") (name "Net-(IC2-SW)") (class "Default")
      (node (ref "C3") (pin "2") (pinfunction "2_2") (pintype "passive"))
      (node (ref "D1") (pin "A") (pinfunction "A_A") (pintype "passive"))
      (node (ref "IC2") (pin "8") (pinfunction "SW_8") (pintype "bidirectional"))
      (node (ref "L3") (pin "2") (pinfunction "2_2") (pintype "passive"))
    )
    (net (code "37") (name "Net-(IC3-PROG)") (class "Default")
      (node (ref "IC3") (pin "5") (pinfunction "PROG_5") (pintype "bidirectional"))
      (node (ref "R15") (pin "1") (pinfunction "1_1") (pintype "passive"))
    )
    (net (code "38") (name "Net-(IC3-STAT)") (class "Default")
      (node (ref "IC3") (pin "1") (pinfunction "STAT_1") (pintype "bidirectional"))
      (node (ref "R16") (pin "2") (pinfunction "2_2") (pintype "passive"))
    )
    (net (code "39") (name "Net-(IC3-VDD)") (class "Default")
      (node (ref "C10") (pin "1") (pinfunction "1_1") (pintype "passive"))
      (node (ref "IC3") (pin "4") (pinfunction "VDD_4") (pintype "bidirectional"))
      (node (ref "LED") (pin "A") (pinfunction "A_A") (pintype "passive"))
      (node (ref "X1") (pin "1") (pinfunction "1_1") (pintype "input"))
    )
    (net (code "40") (name "Net-(IC4-BYPASS)") (class "Default")
      (node (ref "C15") (pin "2") (pinfunction "2_2") (pintype "passive"))
      (node (ref "IC4") (pin "4") (pinfunction "BYPASS_4") (pintype "passive"))
    )
    (net (code "41") (name "Net-(LED-PadC)") (class "Default")
      (node (ref "LED") (pin "C") (pinfunction "C_C") (pintype "passive"))
      (node (ref "R16") (pin "1") (pinfunction "1_1") (pintype "passive"))
    )
    (net (code "42") (name "Net-(PAD3-P)") (class "Default")
      (node (ref "PAD3") (pin "1") (pinfunction "P_1") (pintype "passive"))
      (node (ref "PAD7") (pin "1") (pinfunction "P_1") (pintype "passive"))
      (node (ref "R1") (pin "2") (pinfunction "2_2") (pintype "passive"))
      (node (ref "SEG1") (pin "5") (pinfunction "DP_5") (pintype "passive"))
      (node (ref "SEG2") (pin "5") (pinfunction "DP_5") (pintype "passive"))
    )
    (net (code "43") (name "Net-(PAD4-P)") (class "Default")
      (node (ref "PAD4") (pin "1") (pinfunction "P_1") (pintype "passive"))
      (node (ref "PAD8") (pin "1") (pinfunction "P_1") (pintype "passive"))
      (node (ref "R6") (pin "2") (pinfunction "2_2") (pintype "passive"))
      (node (ref "SEG1") (pin "4") (pinfunction "C_4") (pintype "passive"))
      (node (ref "SEG2") (pin "4") (pinfunction "C_4") (pintype "passive"))
    )
    (net (code "44") (name "Net-(PAD5-P)") (class "Default")
      (node (ref "PAD5") (pin "1") (pinfunction "P_1") (pintype "passive"))
      (node (ref "PAD9") (pin "1") (pinfunction "P_1") (pintype "passive"))
      (node (ref "R5") (pin "2") (pinfunction "2_2") (pintype "passive"))
      (node (ref "SEG1") (pin "2") (pinfunction "D_2") (pintype "passive"))
      (node (ref "SEG2") (pin "2") (pinfunction "D_2") (pintype "passive"))
    )
    (net (code "45") (name "Net-(PAD10-P)") (class "Default")
      (node (ref "PAD10") (pin "1") (pinfunction "P_1") (pintype "passive"))
      (node (ref "PAD6") (pin "1") (pinfunction "P_1") (pintype "passive"))
      (node (ref "R4") (pin "2") (pinfunction "2_2") (pintype "passive"))
      (node (ref "SEG1") (pin "1") (pinfunction "E_1") (pintype "passive"))
      (node (ref "SEG2") (pin "1") (pinfunction "E_1") (pintype "passive"))
    )
    (net (code "46") (name "Net-(PAD11-P)") (class "Default")
      (node (ref "PAD11") (pin "1") (pinfunction "P_1") (pintype "passive"))
      (node (ref "PAD17") (pin "1") (pinfunction "P_1") (pintype "passive"))
      (node (ref "R2") (pin "2") (pinfunction "2_2") (pintype "passive"))
      (node (ref "SEG1") (pin "10") (pinfunction "G_10") (pintype "passive"))
      (node (ref "SEG2") (pin "10") (pinfunction "G_10") (pintype "passive"))
    )
    (net (code "47") (name "Net-(PAD12-P)") (class "Default")
      (node (ref "PAD12") (pin "1") (pinfunction "P_1") (pintype "passive"))
      (node (ref "PAD18") (pin "1") (pinfunction "P_1") (pintype "passive"))
      (node (ref "R3") (pin "2") (pinfunction "2_2") (pintype "passive"))
      (node (ref "SEG1") (pin "9") (pinfunction "F_9") (pintype "passive"))
      (node (ref "SEG2") (pin "9") (pinfunction "F_9") (pintype "passive"))
    )
    (net (code "48") (name "Net-(PAD13-P)") (class "Default")
      (node (ref "PAD13") (pin "1") (pinfunction "P_1") (pintype "passive"))
      (node (ref "PAD19") (pin "1") (pinfunction "P_1") (pintype "passive"))
      (node (ref "R8") (pin "2") (pinfunction "2_2") (pintype "passive"))
      (node (ref "SEG1") (pin "7") (pinfunction "A_7") (pintype "passive"))
      (node (ref "SEG2") (pin "7") (pinfunction "A_7") (pintype "passive"))
    )
    (net (code "49") (name "Net-(PAD14-P)") (class "Default")
      (node (ref "PAD14") (pin "1") (pinfunction "P_1") (pintype "passive"))
      (node (ref "PAD20") (pin "1") (pinfunction "P_1") (pintype "passive"))
      (node (ref "R7") (pin "2") (pinfunction "2_2") (pintype "passive"))
      (node (ref "SEG1") (pin "6") (pinfunction "B_6") (pintype "passive"))
      (node (ref "SEG2") (pin "6") (pinfunction "B_6") (pintype "passive"))
    )
    (net (code "50") (name "Net-(Q1-D)") (class "Default")
      (node (ref "Q1") (pin "3") (pinfunction "D_3") (pintype "passive"))
      (node (ref "R1") (pin "1") (pinfunction "1_1") (pintype "passive"))
    )
    (net (code "51") (name "Net-(Q2-D)") (class "Default")
      (node (ref "Q2") (pin "3") (pinfunction "D_3") (pintype "passive"))
      (node (ref "R2") (pin "1") (pinfunction "1_1") (pintype "passive"))
    )
    (net (code "52") (name "Net-(Q3-D)") (class "Default")
      (node (ref "Q3") (pin "3") (pinfunction "D_3") (pintype "passive"))
      (node (ref "R3") (pin "1") (pinfunction "1_1") (pintype "passive"))
    )
    (net (code "53") (name "Net-(Q4-D)") (class "Default")
      (node (ref "Q4") (pin "3") (pinfunction "D_3") (pintype "passive"))
      (node (ref "R4") (pin "1") (pinfunction "1_1") (pintype "passive"))
    )
    (net (code "54") (name "Net-(Q5-D)") (class "Default")
      (node (ref "Q5") (pin "3") (pinfunction "D_3") (pintype "passive"))
      (node (ref "R5") (pin "1") (pinfunction "1_1") (pintype "passive"))
    )
    (net (code "55") (name "Net-(Q6-D)") (class "Default")
      (node (ref "Q6") (pin "3") (pinfunction "D_3") (pintype "passive"))
      (node (ref "R6") (pin "1") (pinfunction "1_1") (pintype "passive"))
    )
    (net (code "56") (name "Net-(Q7-D)") (class "Default")
      (node (ref "Q7") (pin "3") (pinfunction "D_3") (pintype "passive"))
      (node (ref "R7") (pin "1") (pinfunction "1_1") (pintype "passive"))
    )
    (net (code "57") (name "Net-(Q8-D)") (class "Default")
      (node (ref "Q8") (pin "3") (pinfunction "D_3") (pintype "passive"))
      (node (ref "R8") (pin "1") (pinfunction "1_1") (pintype "passive"))
    )
    (net (code "58") (name "Net-(Q10-D)") (class "Default")
      (node (ref "Q10") (pin "3") (pinfunction "D_3") (pintype "passive"))
      (node (ref "Q9") (pin "1") (pinfunction "G_1") (pintype "passive"))
      (node (ref "R9") (pin "2") (pinfunction "2_2") (pintype "passive"))
    )
    (net (code "59") (name "Net-(Q11-G)") (class "Default")
      (node (ref "Q11") (pin "1") (pinfunction "G_1") (pintype "passive"))
      (node (ref "Q12") (pin "3") (pinfunction "D_3") (pintype "passive"))
      (node (ref "R10") (pin "2") (pinfunction "2_2") (pintype "passive"))
    )
    (net (code "60") (name "Net-(Q13-G)") (class "Default")
      (node (ref "Q13") (pin "1") (pinfunction "G_1") (pintype "passive"))
      (node (ref "Q14") (pin "3") (pinfunction "D_3") (pintype "passive"))
      (node (ref "R11") (pin "2") (pinfunction "2_2") (pintype "passive"))
    )
    (net (code "61") (name "Net-(Q15-G)") (class "Default")
      (node (ref "Q15") (pin "1") (pinfunction "G_1") (pintype "passive"))
      (node (ref "Q16") (pin "3") (pinfunction "D_3") (pintype "passive"))
      (node (ref "R12") (pin "2") (pinfunction "2_2") (pintype "passive"))
    )
    (net (code "62") (name "Net-(Q17-G)") (class "Default")
      (node (ref "D2") (pin "A") (pinfunction "A_A") (pintype "passive"))
      (node (ref "Q17") (pin "1") (pinfunction "G_1") (pintype "passive"))
      (node (ref "Q20") (pin "3") (pinfunction "D_3") (pintype "passive"))
      (node (ref "R19") (pin "2") (pinfunction "2_2") (pintype "passive"))
    )
    (net (code "63") (name "Net-(S4-S)") (class "Default")
      (node (ref "D2") (pin "C") (pinfunction "C_C") (pintype "passive"))
      (node (ref "D3") (pin "C") (pinfunction "C_C") (pintype "passive"))
      (node (ref "S4") (pin "2") (pinfunction "S_2") (pintype "passive"))
    )
    (net (code "64") (name "RFM69_DIO0") (class "Default")
      (node (ref "IC1") (pin "25") (pinfunction "PB12_25") (pintype "bidirectional"))
      (node (ref "U$1") (pin "DIO0") (pinfunction "DIO0_DIO0") (pintype "bidirectional"))
    )
    (net (code "65") (name "RFM69_DIO1") (class "Default")
      (node (ref "IC1") (pin "26") (pinfunction "PB13_26") (pintype "bidirectional"))
      (node (ref "U$1") (pin "DIO1") (pinfunction "DIO1_DIO1") (pintype "bidirectional"))
    )
    (net (code "66") (name "RFM69_DIO2") (class "Default")
      (node (ref "IC1") (pin "27") (pinfunction "PB14_27") (pintype "bidirectional"))
      (node (ref "U$1") (pin "DIO2") (pinfunction "DIO2_DIO2") (pintype "bidirectional"))
    )
    (net (code "67") (name "RFM69_DIO3") (class "Default")
      (node (ref "IC1") (pin "28") (pinfunction "PB15_28") (pintype "bidirectional"))
      (node (ref "U$1") (pin "DIO3") (pinfunction "DIO3_DIO3") (pintype "bidirectional"))
    )
    (net (code "68") (name "RFM69_DIO4") (class "Default")
      (node (ref "IC1") (pin "29") (pinfunction "PA8_29") (pintype "bidirectional"))
      (node (ref "U$1") (pin "DIO4") (pinfunction "DIO4_DIO4") (pintype "bidirectional"))
    )
    (net (code "69") (name "RFM69_DIO5") (class "Default")
      (node (ref "IC1") (pin "30") (pinfunction "PA9_30") (pintype "bidirectional"))
      (node (ref "U$1") (pin "DIO5") (pinfunction "DIO5_DIO5") (pintype "bidirectional"))
    )
    (net (code "70") (name "SCK") (class "Default")
      (node (ref "IC1") (pin "39") (pinfunction "PB3_39") (pintype "bidirectional"))
      (node (ref "M1") (pin "5") (pinfunction "SCK_5") (pintype "bidirectional"))
      (node (ref "U$1") (pin "SCK") (pinfunction "SCK_SCK") (pintype "bidirectional"))
    )
    (net (code "71") (name "SWITCH") (class "Default")
      (node (ref "D3") (pin "A") (pinfunction "A_A") (pintype "passive"))
      (node (ref "IC1") (pin "3") (pinfunction "PC14_3") (pintype "bidirectional"))
    )
    (net (code "72") (name "S_A") (class "Default")
      (node (ref "IC1") (pin "19") (pinfunction "PB1_19") (pintype "bidirectional"))
      (node (ref "Q8") (pin "1") (pinfunction "G_1") (pintype "passive"))
    )
    (net (code "73") (name "S_B") (class "Default")
      (node (ref "IC1") (pin "20") (pinfunction "PB2_20") (pintype "bidirectional"))
      (node (ref "Q7") (pin "1") (pinfunction "G_1") (pintype "passive"))
    )
    (net (code "74") (name "S_C") (class "Default")
      (node (ref "IC1") (pin "35") (pinfunction "PF6_35") (pintype "bidirectional"))
      (node (ref "Q5") (pin "1") (pinfunction "G_1") (pintype "passive"))
    )
    (net (code "75") (name "S_D") (class "Default")
      (node (ref "IC1") (pin "45") (pinfunction "PB8_45") (pintype "bidirectional"))
      (node (ref "Q6") (pin "1") (pinfunction "G_1") (pintype "passive"))
    )
    (net (code "76") (name "S_DOT") (class "Default")
      (node (ref "IC1") (pin "38") (pinfunction "PA15_38") (pintype "bidirectional"))
      (node (ref "Q4") (pin "1") (pinfunction "G_1") (pintype "passive"))
    )
    (net (code "77") (name "S_E") (class "Default")
      (node (ref "IC1") (pin "46") (pinfunction "PB9_46") (pintype "bidirectional"))
      (node (ref "Q1") (pin "1") (pinfunction "G_1") (pintype "passive"))
    )
    (net (code "78") (name "S_F") (class "Default")
      (node (ref "IC1") (pin "18") (pinfunction "PB0_18") (pintype "bidirectional"))
      (node (ref "Q3") (pin "1") (pinfunction "G_1") (pintype "passive"))
    )
    (net (code "79") (name "S_G") (class "Default")
      (node (ref "IC1") (pin "17") (pinfunction "PA7_17") (pintype "bidirectional"))
      (node (ref "Q2") (pin "1") (pinfunction "G_1") (pintype "passive"))
    )
    (net (code "80") (name "V+") (class "Default")
      (node (ref "BAT1") (pin "+") (pinfunction "+_+") (pintype "passive"))
      (node (ref "C9") (pin "1") (pinfunction "1_1") (pintype "passive"))
      (node (ref "IC3") (pin "3") (pinfunction "VBAT_3") (pintype "bidirectional"))
      (node (ref "Q17") (pin "2") (pinfunction "S_2") (pintype "passive"))
      (node (ref "R19") (pin "1") (pinfunction "1_1") (pintype "passive"))
    )
    (net (code "81") (name "VCC") (class "Default")
      (node (ref "C13") (pin "1") (pinfunction "1_1") (pintype "passive"))
      (node (ref "C7") (pin "+") (pinfunction "+_+") (pintype "passive"))
      (node (ref "IC2") (pin "6") (pinfunction "VDD_6") (pintype "bidirectional"))
      (node (ref "IC4") (pin "1") (pinfunction "VIN_1") (pintype "power_in"))
      (node (ref "IC4") (pin "3") (pinfunction "ON_3") (pintype "input"))
      (node (ref "L3") (pin "1") (pinfunction "1_1") (pintype "passive"))
      (node (ref "Q17") (pin "3") (pinfunction "D_3") (pintype "passive"))
      (node (ref "R13") (pin "2") (pinfunction "2_2") (pintype "passive"))
      (node (ref "R23") (pin "1") (pinfunction "1_1") (pintype "passive"))
    )
    (net (code "82") (name "VDD") (class "Default")
      (node (ref "C1") (pin "1") (pinfunction "1_1") (pintype "passive"))
      (node (ref "C14") (pin "1") (pinfunction "1_1") (pintype "passive"))
      (node (ref "C2") (pin "1") (pinfunction "1_1") (pintype "passive"))
      (node (ref "IC1") (pin "1") (pinfunction "VDD_1") (pintype "power_in"))
      (node (ref "IC1") (pin "24") (pinfunction "VDD_24") (pintype "power_in"))
      (node (ref "IC1") (pin "48") (pinfunction "VDD_48") (pintype "power_in"))
      (node (ref "IC4") (pin "5") (pinfunction "VOUT_5") (pintype "output"))
      (node (ref "L2") (pin "1") (pinfunction "1_1") (pintype "passive"))
      (node (ref "M1") (pin "2") (pinfunction "VCC_2") (pintype "power_in"))
      (node (ref "SWD") (pin "1") (pinfunction "1_1") (pintype "passive"))
      (node (ref "U$1") (pin "VCC") (pinfunction "VCC_VCC") (pintype "bidirectional"))
    )
    (net (code "83") (name "unconnected-(PAD1-P-Pad1)") (class "Default")
      (node (ref "PAD1") (pin "1") (pinfunction "P_1") (pintype "passive"))
    )
    (net (code "84") (name "unconnected-(PAD2-P-Pad1)") (class "Default")
      (node (ref "PAD2") (pin "1") (pinfunction "P_1") (pintype "passive"))
    )
    (net (code "85") (name "unconnected-(SEG1-COM-Pad3)") (class "Default")
      (node (ref "SEG1") (pin "3") (pinfunction "COM_3") (pintype "passive"))
    )
    (net (code "86") (name "unconnected-(SEG2-COM-Pad3)") (class "Default")
      (node (ref "SEG2") (pin "3") (pinfunction "COM_3") (pintype "passive"))
    )
    (net (code "87") (name "unconnected-(U$1-PadNC)") (class "Default")
      (node (ref "U$1") (pin "NC") (pinfunction "NC_NC") (pintype "bidirectional"))
    )
    (net (code "88") (name "unconnected-(U$1-PadRESET)") (class "Default")
      (node (ref "U$1") (pin "RESET") (pinfunction "RESET_RESET") (pintype "bidirectional"))
    )
    (net (code "89") (name "unconnected-(X1-Pad2)") (class "Default")
      (node (ref "X1") (pin "2") (pinfunction "2_2") (pintype "input"))
    )
    (net (code "90") (name "unconnected-(X1-Pad3)") (class "Default")
      (node (ref "X1") (pin "3") (pinfunction "3_3") (pintype "input"))
    )
    (net (code "91") (name "unconnected-(X1-Pad4)") (class "Default")
      (node (ref "X1") (pin "4") (pinfunction "4_4") (pintype "input"))
    )
  )
)
